# TinyGame_RC1_Jig.net
KiCad netlist of a schematic drawn in EAGLE
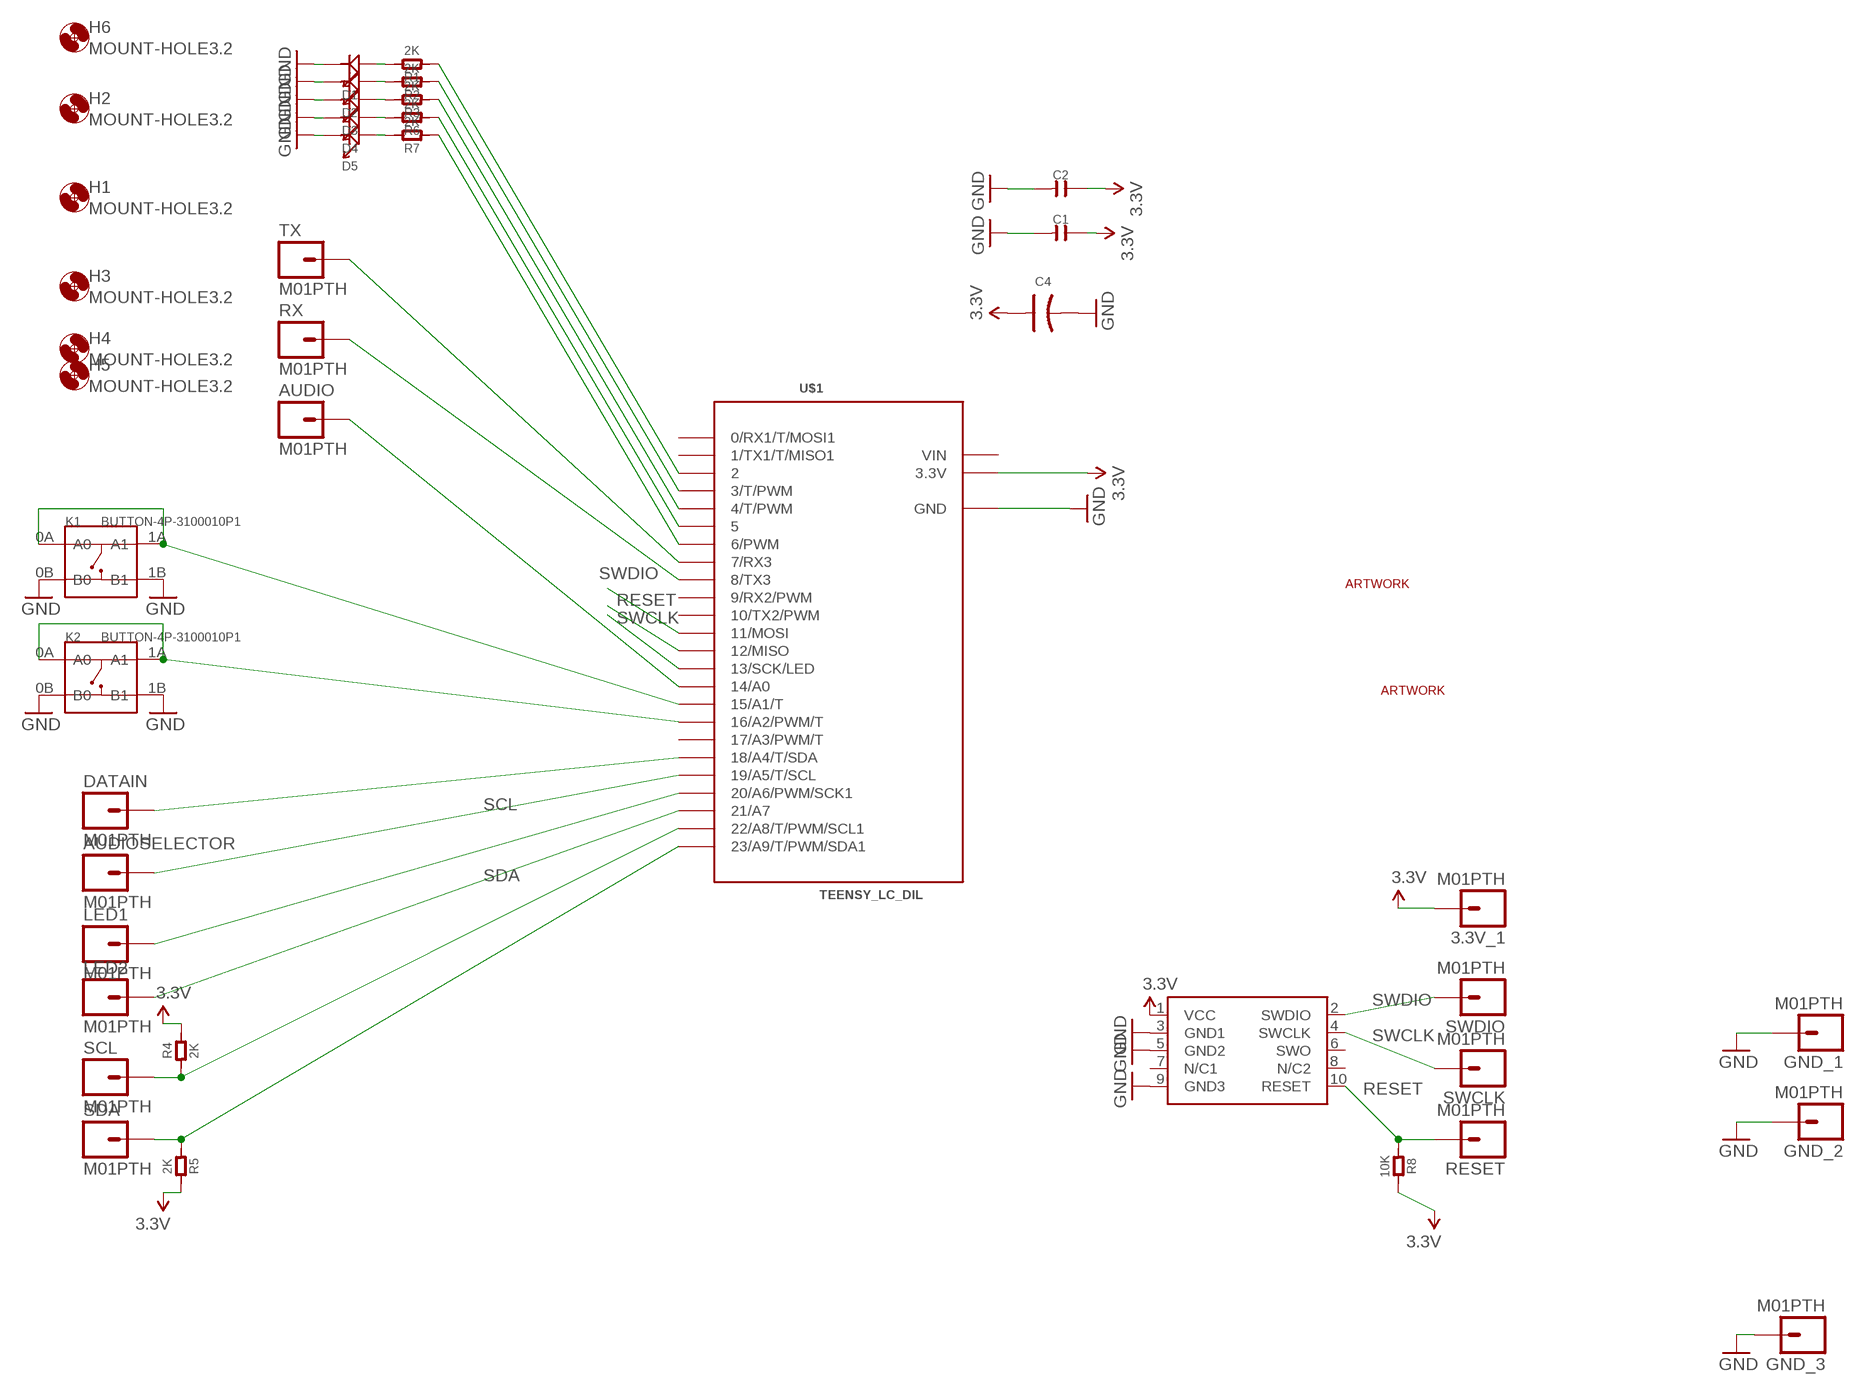
[diagram p0: schematic, sheet 1]

(export (version "E")
  (design (tool "Eeschema 10.0.6"))
  (components
    (comp (ref "3.3V_1")
      (value "M01PTH")
      (footprint "eagle-import:1X01")
      (libsource (lib "eagle-import") (part "M01PTH"))
    )
    (comp (ref "AUDIO")
      (value "M01PTH")
      (footprint "eagle-import:1X01")
      (libsource (lib "eagle-import") (part "M01PTH"))
    )
    (comp (ref "AUDIOSELECTOR")
      (value "M01PTH")
      (footprint "eagle-import:1X01")
      (libsource (lib "eagle-import") (part "M01PTH"))
    )
    (comp (ref "C1")
      (value "C-0603")
      (footprint "eagle-import:C0603")
      (libsource (lib "eagle-import") (part "C-0603"))
    )
    (comp (ref "C2")
      (value "C-0603")
      (footprint "eagle-import:C0603")
      (libsource (lib "eagle-import") (part "C-0603"))
    )
    (comp (ref "C4")
      (value "C-POLAR-A")
      (footprint "eagle-import:AVX-A")
      (libsource (lib "eagle-import") (part "C-POLAR-A"))
    )
    (comp (ref "D1")
      (value "LED")
      (footprint "eagle-import:LED0603")
      (libsource (lib "eagle-import") (part "LED"))
    )
    (comp (ref "D2")
      (value "LED")
      (footprint "eagle-import:LED0603")
      (libsource (lib "eagle-import") (part "LED"))
    )
    (comp (ref "D3")
      (value "LED")
      (footprint "eagle-import:LED0603")
      (libsource (lib "eagle-import") (part "LED"))
    )
    (comp (ref "D4")
      (value "LED")
      (footprint "eagle-import:LED0603")
      (libsource (lib "eagle-import") (part "LED"))
    )
    (comp (ref "D5")
      (value "LED")
      (footprint "eagle-import:LED0603")
      (libsource (lib "eagle-import") (part "LED"))
    )
    (comp (ref "DATAIN")
      (value "M01PTH")
      (footprint "eagle-import:1X01")
      (libsource (lib "eagle-import") (part "M01PTH"))
    )
    (comp (ref "GND_1")
      (value "M01PTH")
      (footprint "eagle-import:1X01")
      (libsource (lib "eagle-import") (part "M01PTH"))
    )
    (comp (ref "GND_2")
      (value "M01PTH")
      (footprint "eagle-import:1X01")
      (libsource (lib "eagle-import") (part "M01PTH"))
    )
    (comp (ref "GND_3")
      (value "M01PTH")
      (footprint "eagle-import:1X01")
      (libsource (lib "eagle-import") (part "M01PTH"))
    )
    (comp (ref "H1")
      (value "MOUNT-HOLE3.2")
      (footprint "eagle-import:3,2")
      (libsource (lib "eagle-import") (part "MOUNT-HOLE3.2"))
    )
    (comp (ref "H2")
      (value "MOUNT-HOLE3.2")
      (footprint "eagle-import:3,2")
      (libsource (lib "eagle-import") (part "MOUNT-HOLE3.2"))
    )
    (comp (ref "H3")
      (value "MOUNT-HOLE3.2")
      (footprint "eagle-import:3,2")
      (libsource (lib "eagle-import") (part "MOUNT-HOLE3.2"))
    )
    (comp (ref "H4")
      (value "MOUNT-HOLE3.2")
      (footprint "eagle-import:3,2")
      (libsource (lib "eagle-import") (part "MOUNT-HOLE3.2"))
    )
    (comp (ref "H5")
      (value "MOUNT-HOLE3.2")
      (footprint "eagle-import:3,2")
      (libsource (lib "eagle-import") (part "MOUNT-HOLE3.2"))
    )
    (comp (ref "H6")
      (value "MOUNT-HOLE3.2")
      (footprint "eagle-import:3,2")
      (libsource (lib "eagle-import") (part "MOUNT-HOLE3.2"))
    )
    (comp (ref "K1")
      (value "BUTTON-4P-3100010P1")
      (footprint "eagle-import:4P-SMD-6.0X6.0X5.0H")
      (libsource (lib "eagle-import") (part "BUTTON-4P-3100010P1"))
    )
    (comp (ref "K2")
      (value "BUTTON-4P-3100010P1")
      (footprint "eagle-import:4P-SMD-6.0X6.0X5.0H")
      (libsource (lib "eagle-import") (part "BUTTON-4P-3100010P1"))
    )
    (comp (ref "LED1")
      (value "M01PTH")
      (footprint "eagle-import:1X01")
      (libsource (lib "eagle-import") (part "M01PTH"))
    )
    (comp (ref "LED2")
      (value "M01PTH")
      (footprint "eagle-import:1X01")
      (libsource (lib "eagle-import") (part "M01PTH"))
    )
    (comp (ref "R1")
      (value "2K")
      (footprint "eagle-import:R0603")
      (libsource (lib "eagle-import") (part "R-0603"))
    )
    (comp (ref "R2")
      (value "2K")
      (footprint "eagle-import:R0603")
      (libsource (lib "eagle-import") (part "R-0603"))
    )
    (comp (ref "R3")
      (value "2K")
      (footprint "eagle-import:R0603")
      (libsource (lib "eagle-import") (part "R-0603"))
    )
    (comp (ref "R4")
      (value "2K")
      (footprint "eagle-import:R0603")
      (libsource (lib "eagle-import") (part "R-0603"))
    )
    (comp (ref "R5")
      (value "2K")
      (footprint "eagle-import:R0603")
      (libsource (lib "eagle-import") (part "R-0603"))
    )
    (comp (ref "R6")
      (value "2K")
      (footprint "eagle-import:R0603")
      (libsource (lib "eagle-import") (part "R-0603"))
    )
    (comp (ref "R7")
      (value "2K")
      (footprint "eagle-import:R0603")
      (libsource (lib "eagle-import") (part "R-0603"))
    )
    (comp (ref "R8")
      (value "10K")
      (footprint "eagle-import:R0603")
      (libsource (lib "eagle-import") (part "R-0603"))
    )
    (comp (ref "RESET")
      (value "M01PTH")
      (footprint "eagle-import:1X01")
      (libsource (lib "eagle-import") (part "M01PTH"))
    )
    (comp (ref "RX")
      (value "M01PTH")
      (footprint "eagle-import:1X01")
      (libsource (lib "eagle-import") (part "M01PTH"))
    )
    (comp (ref "SCL")
      (value "M01PTH")
      (footprint "eagle-import:1X01")
      (libsource (lib "eagle-import") (part "M01PTH"))
    )
    (comp (ref "SDA")
      (value "M01PTH")
      (footprint "eagle-import:1X01")
      (libsource (lib "eagle-import") (part "M01PTH"))
    )
    (comp (ref "SWCLK")
      (value "M01PTH")
      (footprint "eagle-import:1X01")
      (libsource (lib "eagle-import") (part "M01PTH"))
    )
    (comp (ref "SWD1")
      (value "CORTEX_SWDVERT")
      (footprint "eagle-import:SWD_VERTICAL")
      (libsource (lib "eagle-import") (part "CORTEX_SWDVERT"))
    )
    (comp (ref "SWDIO")
      (value "M01PTH")
      (footprint "eagle-import:1X01")
      (libsource (lib "eagle-import") (part "M01PTH"))
    )
    (comp (ref "TX")
      (value "M01PTH")
      (footprint "eagle-import:1X01")
      (libsource (lib "eagle-import") (part "M01PTH"))
    )
    (comp (ref "U$1")
      (value "TEENSY_LC_DIL")
      (footprint "eagle-import:TEENSY_3.0-3.2&LC_DIL")
      (libsource (lib "eagle-import") (part "TEENSY_LC_DIL"))
    )
    (comp (ref "U$2")
      (value "TINRS_ARTWORKLOGO")
      (footprint "eagle-import:TINRSLOGO")
      (libsource (lib "eagle-import") (part "TINRS_ARTWORKLOGO"))
    )
    (comp (ref "U$3")
      (value "TINRS_ARTWORKROCKET")
      (footprint "eagle-import:TINRS_ROCKET")
      (libsource (lib "eagle-import") (part "TINRS_ARTWORKROCKET"))
    )
  )
  (nets
    (net (code "1") (name "/RESET") (class "Default")
      (node (ref "R8") (pin "1") (pinfunction "1_1") (pintype "bidirectional"))
      (node (ref "RESET") (pin "1") (pinfunction "1_1") (pintype "passive"))
      (node (ref "SWD1") (pin "10") (pinfunction "RESET_10") (pintype "bidirectional"))
      (node (ref "U$1") (pin "12") (pinfunction "12/MISO_12") (pintype "bidirectional"))
    )
    (net (code "2") (name "/SCL") (class "Default")
      (node (ref "R4") (pin "1") (pinfunction "1_1") (pintype "bidirectional"))
      (node (ref "SCL") (pin "1") (pinfunction "1_1") (pintype "passive"))
      (node (ref "U$1") (pin "22/A8") (pinfunction "22/A8/T/PWM/SCL1_22/A8") (pintype "bidirectional"))
    )
    (net (code "3") (name "/SDA") (class "Default")
      (node (ref "R5") (pin "1") (pinfunction "1_1") (pintype "bidirectional"))
      (node (ref "SDA") (pin "1") (pinfunction "1_1") (pintype "passive"))
      (node (ref "U$1") (pin "23/A9") (pinfunction "23/A9/T/PWM/SDA1_23/A9") (pintype "bidirectional"))
    )
    (net (code "4") (name "/SWCLK") (class "Default")
      (node (ref "SWCLK") (pin "1") (pinfunction "1_1") (pintype "passive"))
      (node (ref "SWD1") (pin "4") (pinfunction "SWCLK_4") (pintype "bidirectional"))
      (node (ref "U$1") (pin "13") (pinfunction "13/SCK/LED_13") (pintype "bidirectional"))
    )
    (net (code "5") (name "/SWDIO") (class "Default")
      (node (ref "SWD1") (pin "2") (pinfunction "SWDIO_2") (pintype "bidirectional"))
      (node (ref "SWDIO") (pin "1") (pinfunction "1_1") (pintype "passive"))
      (node (ref "U$1") (pin "11") (pinfunction "11/MOSI_11") (pintype "bidirectional"))
    )
    (net (code "6") (name "/VIN") (class "Default")
      (node (ref "U$1") (pin "VIN") (pinfunction "VIN_VIN") (pintype "power_in"))
    )
    (net (code "7") (name "3.3V") (class "Default")
      (node (ref "3.3V_1") (pin "1") (pinfunction "1_1") (pintype "passive"))
      (node (ref "C1") (pin "2") (pinfunction "2_2") (pintype "bidirectional"))
      (node (ref "C2") (pin "2") (pinfunction "2_2") (pintype "bidirectional"))
      (node (ref "C4") (pin "+") (pinfunction "1_+") (pintype "bidirectional"))
      (node (ref "R4") (pin "2") (pinfunction "2_2") (pintype "bidirectional"))
      (node (ref "R5") (pin "2") (pinfunction "2_2") (pintype "bidirectional"))
      (node (ref "R8") (pin "2") (pinfunction "2_2") (pintype "bidirectional"))
      (node (ref "SWD1") (pin "1") (pinfunction "VCC_1") (pintype "bidirectional"))
      (node (ref "U$1") (pin "3.3V") (pinfunction "3.3V_3.3V") (pintype "power_in"))
    )
    (net (code "8") (name "GND") (class "Default")
      (node (ref "C1") (pin "1") (pinfunction "1_1") (pintype "bidirectional"))
      (node (ref "C2") (pin "1") (pinfunction "1_1") (pintype "bidirectional"))
      (node (ref "C4") (pin "-") (pinfunction "2_-") (pintype "bidirectional"))
      (node (ref "D1") (pin "-") (pinfunction "-_-") (pintype "passive"))
      (node (ref "D2") (pin "-") (pinfunction "-_-") (pintype "passive"))
      (node (ref "D3") (pin "-") (pinfunction "-_-") (pintype "passive"))
      (node (ref "D4") (pin "-") (pinfunction "-_-") (pintype "passive"))
      (node (ref "D5") (pin "-") (pinfunction "-_-") (pintype "passive"))
      (node (ref "GND_1") (pin "1") (pinfunction "1_1") (pintype "passive"))
      (node (ref "GND_2") (pin "1") (pinfunction "1_1") (pintype "passive"))
      (node (ref "GND_3") (pin "1") (pinfunction "1_1") (pintype "passive"))
      (node (ref "K1") (pin "0B") (pinfunction "B0_0B") (pintype "bidirectional"))
      (node (ref "K1") (pin "1B") (pinfunction "B1_1B") (pintype "bidirectional"))
      (node (ref "K2") (pin "0B") (pinfunction "B0_0B") (pintype "bidirectional"))
      (node (ref "K2") (pin "1B") (pinfunction "B1_1B") (pintype "bidirectional"))
      (node (ref "SWD1") (pin "3") (pinfunction "GND1_3") (pintype "bidirectional"))
      (node (ref "SWD1") (pin "5") (pinfunction "GND2_5") (pintype "bidirectional"))
      (node (ref "SWD1") (pin "9") (pinfunction "GND3_9") (pintype "bidirectional"))
      (node (ref "U$1") (pin "AGND") (pinfunction "GND_AGND") (pintype "power_in"))
      (node (ref "U$1") (pin "GND") (pinfunction "GND_GND") (pintype "power_in"))
    )
    (net (code "9") (name "Net-(AUDIO-Pad1)") (class "Default")
      (node (ref "AUDIO") (pin "1") (pinfunction "1_1") (pintype "passive"))
      (node (ref "U$1") (pin "14/A0") (pinfunction "14/A0_14/A0") (pintype "bidirectional"))
    )
    (net (code "10") (name "Net-(D1-Pad+)") (class "Default")
      (node (ref "D1") (pin "+") (pinfunction "+_+") (pintype "passive"))
      (node (ref "R1") (pin "2") (pinfunction "2_2") (pintype "bidirectional"))
    )
    (net (code "11") (name "Net-(D2-Pad+)") (class "Default")
      (node (ref "D2") (pin "+") (pinfunction "+_+") (pintype "passive"))
      (node (ref "R2") (pin "2") (pinfunction "2_2") (pintype "bidirectional"))
    )
    (net (code "12") (name "Net-(D3-Pad+)") (class "Default")
      (node (ref "D3") (pin "+") (pinfunction "+_+") (pintype "passive"))
      (node (ref "R3") (pin "2") (pinfunction "2_2") (pintype "bidirectional"))
    )
    (net (code "13") (name "Net-(D4-Pad+)") (class "Default")
      (node (ref "D4") (pin "+") (pinfunction "+_+") (pintype "passive"))
      (node (ref "R6") (pin "2") (pinfunction "2_2") (pintype "bidirectional"))
    )
    (net (code "14") (name "Net-(D5-Pad+)") (class "Default")
      (node (ref "D5") (pin "+") (pinfunction "+_+") (pintype "passive"))
      (node (ref "R7") (pin "2") (pinfunction "2_2") (pintype "bidirectional"))
    )
    (net (code "15") (name "Net-(K1-A0)") (class "Default")
      (node (ref "K1") (pin "0A") (pinfunction "A0_0A") (pintype "bidirectional"))
      (node (ref "K1") (pin "1A") (pinfunction "A1_1A") (pintype "bidirectional"))
      (node (ref "U$1") (pin "15/A1") (pinfunction "15/A1/T_15/A1") (pintype "bidirectional"))
    )
    (net (code "16") (name "Net-(K2-A0)") (class "Default")
      (node (ref "K2") (pin "0A") (pinfunction "A0_0A") (pintype "bidirectional"))
      (node (ref "K2") (pin "1A") (pinfunction "A1_1A") (pintype "bidirectional"))
      (node (ref "U$1") (pin "16/A2") (pinfunction "16/A2/PWM/T_16/A2") (pintype "bidirectional"))
    )
    (net (code "17") (name "Net-(LED2-Pad1)") (class "Default")
      (node (ref "LED2") (pin "1") (pinfunction "1_1") (pintype "passive"))
      (node (ref "U$1") (pin "21/A7") (pinfunction "21/A7_21/A7") (pintype "bidirectional"))
    )
    (net (code "18") (name "Net-(R1-Pad1)") (class "Default")
      (node (ref "R1") (pin "1") (pinfunction "1_1") (pintype "bidirectional"))
      (node (ref "U$1") (pin "2") (pinfunction "2_2") (pintype "bidirectional"))
    )
    (net (code "19") (name "Net-(R6-Pad1)") (class "Default")
      (node (ref "R6") (pin "1") (pinfunction "1_1") (pintype "bidirectional"))
      (node (ref "U$1") (pin "5") (pinfunction "5_5") (pintype "bidirectional"))
    )
    (net (code "20") (name "Net-(U$1-3{slash}T{slash}PWM)") (class "Default")
      (node (ref "R2") (pin "1") (pinfunction "1_1") (pintype "bidirectional"))
      (node (ref "U$1") (pin "3") (pinfunction "3/T/PWM_3") (pintype "bidirectional"))
    )
    (net (code "21") (name "Net-(U$1-4{slash}T{slash}PWM)") (class "Default")
      (node (ref "R3") (pin "1") (pinfunction "1_1") (pintype "bidirectional"))
      (node (ref "U$1") (pin "4") (pinfunction "4/T/PWM_4") (pintype "bidirectional"))
    )
    (net (code "22") (name "Net-(U$1-6{slash}PWM)") (class "Default")
      (node (ref "R7") (pin "1") (pinfunction "1_1") (pintype "bidirectional"))
      (node (ref "U$1") (pin "6") (pinfunction "6/PWM_6") (pintype "bidirectional"))
    )
    (net (code "23") (name "Net-(U$1-7{slash}RX3)") (class "Default")
      (node (ref "TX") (pin "1") (pinfunction "1_1") (pintype "passive"))
      (node (ref "U$1") (pin "7") (pinfunction "7/RX3_7") (pintype "bidirectional"))
    )
    (net (code "24") (name "Net-(U$1-8{slash}TX3)") (class "Default")
      (node (ref "RX") (pin "1") (pinfunction "1_1") (pintype "passive"))
      (node (ref "U$1") (pin "8") (pinfunction "8/TX3_8") (pintype "bidirectional"))
    )
    (net (code "25") (name "Net-(U$1-18{slash}A4{slash}T{slash}SDA)") (class "Default")
      (node (ref "DATAIN") (pin "1") (pinfunction "1_1") (pintype "passive"))
      (node (ref "U$1") (pin "18/A4") (pinfunction "18/A4/T/SDA_18/A4") (pintype "bidirectional"))
    )
    (net (code "26") (name "Net-(U$1-19{slash}A5{slash}T{slash}SCL)") (class "Default")
      (node (ref "AUDIOSELECTOR") (pin "1") (pinfunction "1_1") (pintype "passive"))
      (node (ref "U$1") (pin "19/A5") (pinfunction "19/A5/T/SCL_19/A5") (pintype "bidirectional"))
    )
    (net (code "27") (name "Net-(U$1-20{slash}A6{slash}PWM{slash}SCK1)") (class "Default")
      (node (ref "LED1") (pin "1") (pinfunction "1_1") (pintype "passive"))
      (node (ref "U$1") (pin "20/A6") (pinfunction "20/A6/PWM/SCK1_20/A6") (pintype "bidirectional"))
    )
    (net (code "28") (name "unconnected-(SWD1-N{slash}C1-Pad7)") (class "Default")
      (node (ref "SWD1") (pin "7") (pinfunction "N/C1_7") (pintype "bidirectional"))
    )
    (net (code "29") (name "unconnected-(SWD1-N{slash}C2-Pad8)") (class "Default")
      (node (ref "SWD1") (pin "8") (pinfunction "N/C2_8") (pintype "bidirectional"))
    )
    (net (code "30") (name "unconnected-(SWD1-SWO-Pad6)") (class "Default")
      (node (ref "SWD1") (pin "6") (pinfunction "SWO_6") (pintype "bidirectional"))
    )
    (net (code "31") (name "unconnected-(U$1-0{slash}RX1{slash}T{slash}MOSI1-Pad0)") (class "Default")
      (node (ref "U$1") (pin "0") (pinfunction "0/RX1/T/MOSI1_0") (pintype "bidirectional"))
    )
    (net (code "32") (name "unconnected-(U$1-1{slash}TX1{slash}T{slash}MISO1-Pad1)") (class "Default")
      (node (ref "U$1") (pin "1") (pinfunction "1/TX1/T/MISO1_1") (pintype "bidirectional"))
    )
    (net (code "33") (name "unconnected-(U$1-9{slash}RX2{slash}PWM-Pad9)") (class "Default")
      (node (ref "U$1") (pin "9") (pinfunction "9/RX2/PWM_9") (pintype "bidirectional"))
    )
    (net (code "34") (name "unconnected-(U$1-10{slash}TX2{slash}PWM-Pad10)") (class "Default")
      (node (ref "U$1") (pin "10") (pinfunction "10/TX2/PWM_10") (pintype "bidirectional"))
    )
    (net (code "35") (name "unconnected-(U$1-17{slash}A3{slash}PWM{slash}T-Pad17{slash}A3)") (class "Default")
      (node (ref "U$1") (pin "17/A3") (pinfunction "17/A3/PWM/T_17/A3") (pintype "bidirectional"))
    )
  )
)
